# SolderDispenser_v1_3.net
KiCad netlist of a schematic drawn in EAGLE
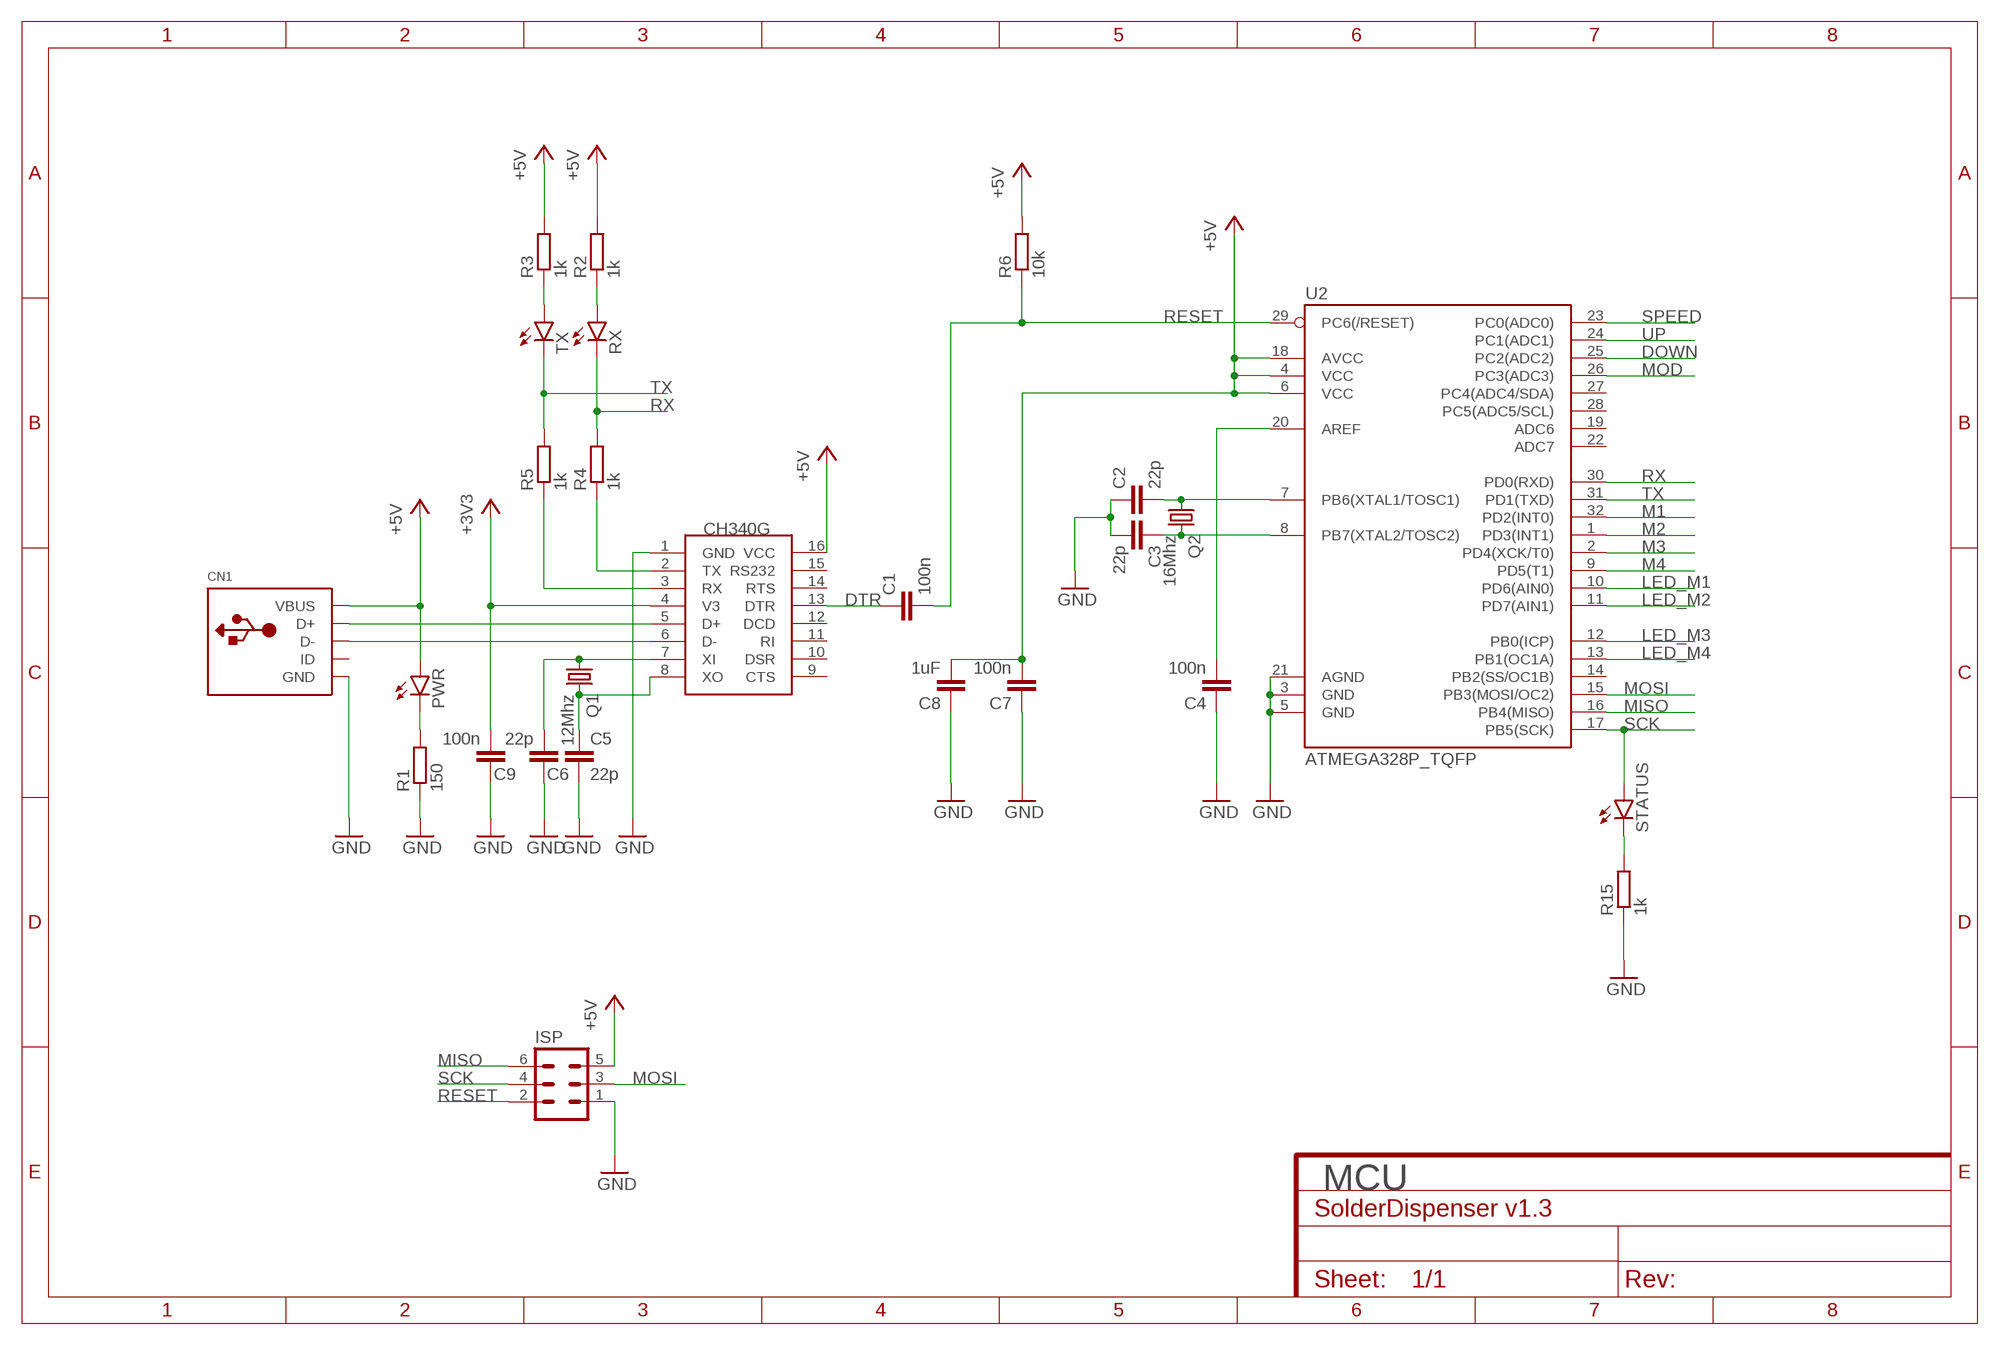
[diagram p0: schematic, sheet 1, part 1 of 2]
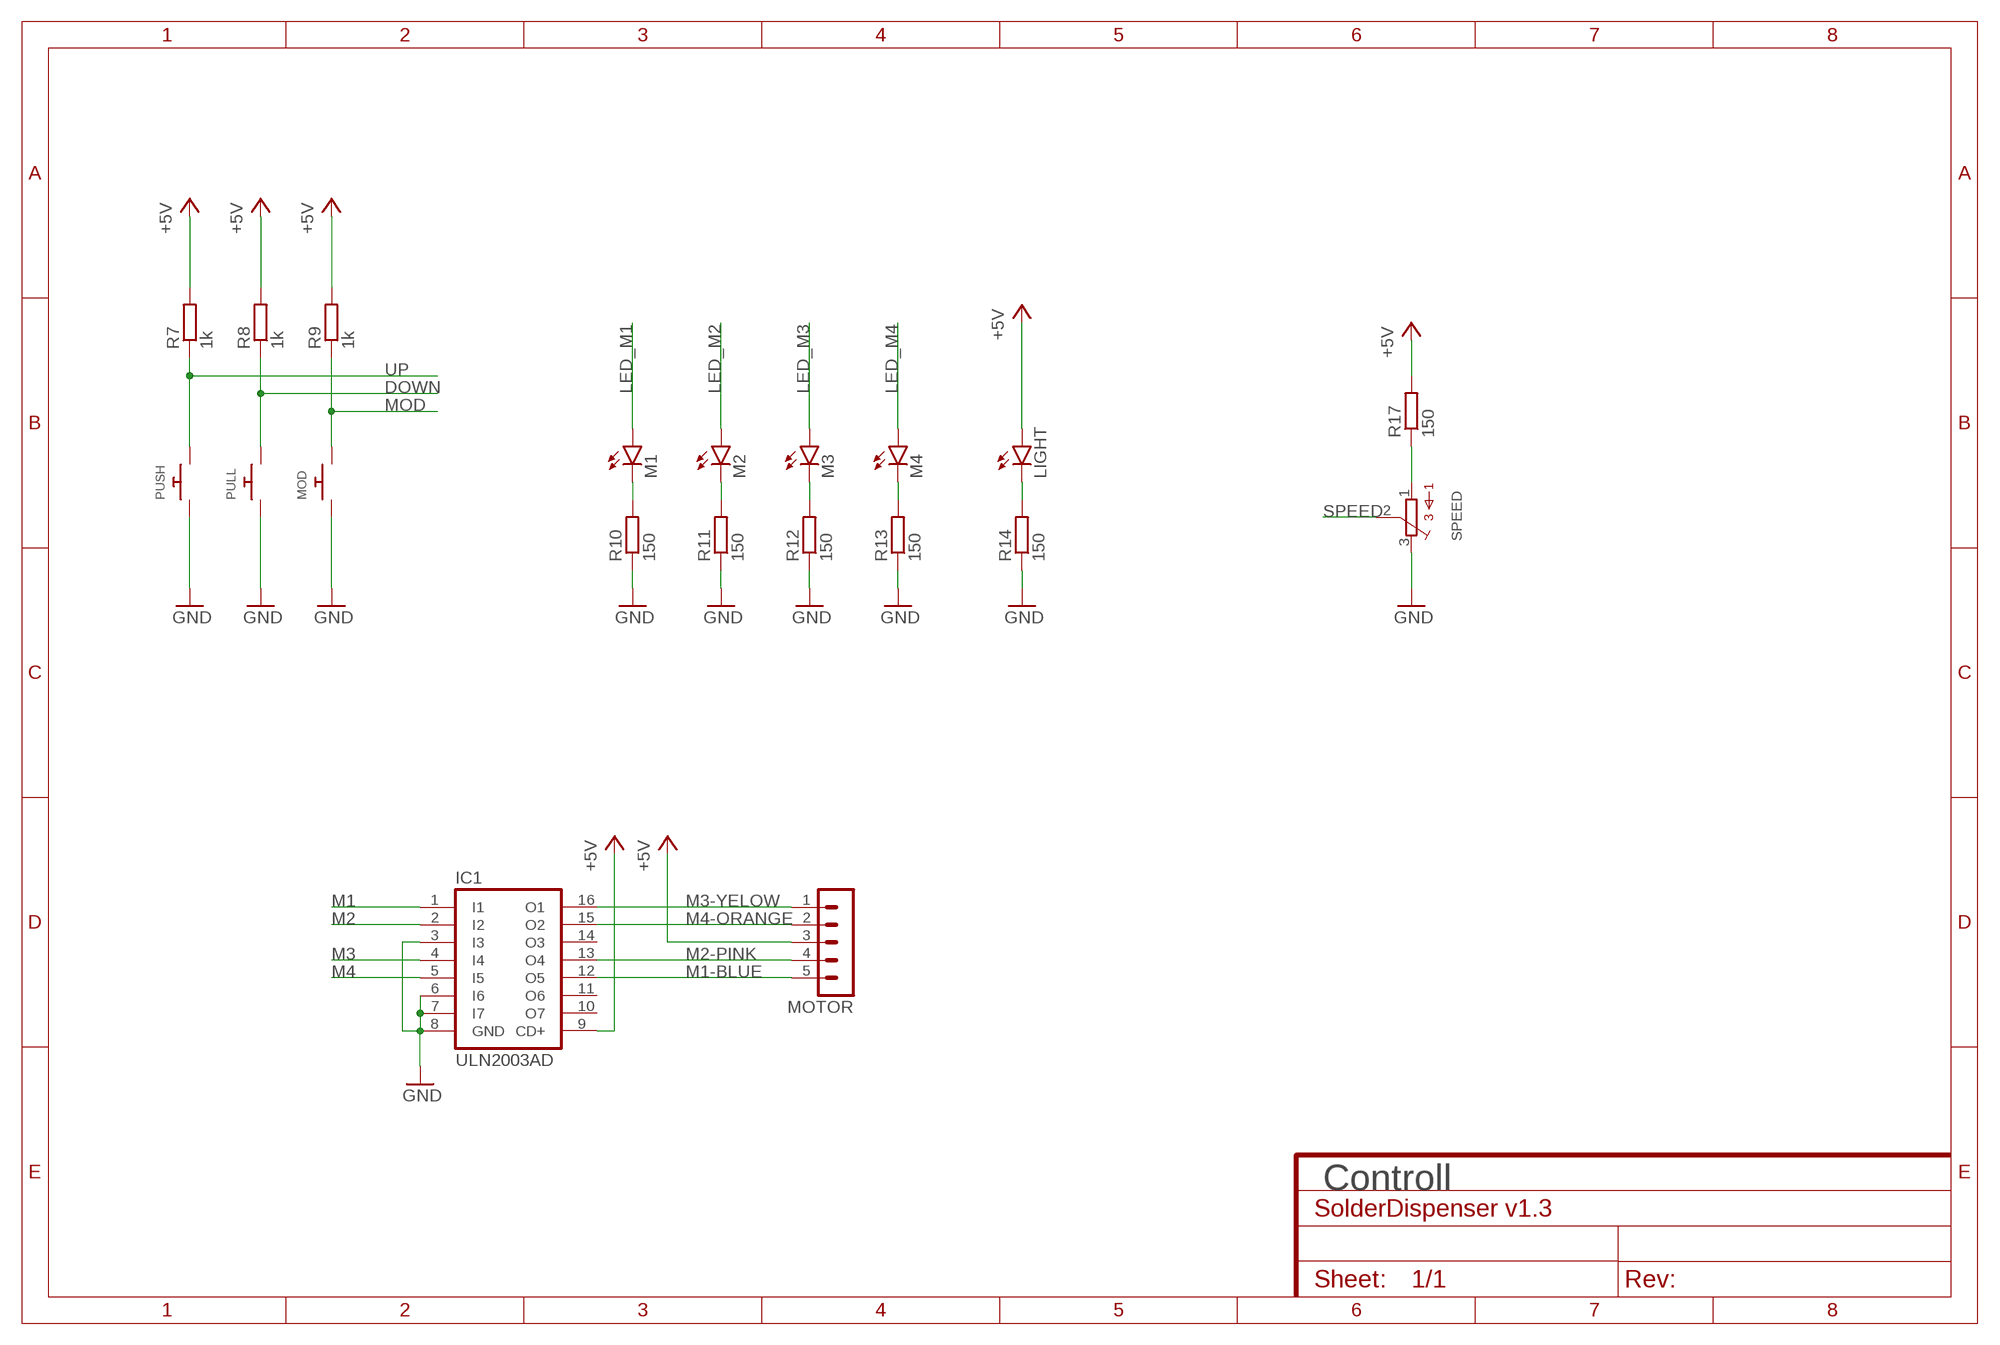
[diagram p1: schematic, sheet 1, part 2 of 2]

(export (version "E")
  (design (tool "Eeschema 10.0.6"))
  (components
    (comp (ref "C1")
      (value "100n")
      (footprint "eagle-import:C0805")
      (libsource (lib "eagle-import") (part "C-EUC0805"))
    )
    (comp (ref "C2")
      (value "22p")
      (footprint "eagle-import:C0805")
      (libsource (lib "eagle-import") (part "C-EUC0805"))
    )
    (comp (ref "C3")
      (value "22p")
      (footprint "eagle-import:C0805")
      (libsource (lib "eagle-import") (part "C-EUC0805"))
    )
    (comp (ref "C4")
      (value "100n")
      (footprint "eagle-import:C0805")
      (libsource (lib "eagle-import") (part "C-EUC0805"))
    )
    (comp (ref "C5")
      (value "22p")
      (footprint "eagle-import:C0805")
      (libsource (lib "eagle-import") (part "C-EUC0805"))
    )
    (comp (ref "C6")
      (value "22p")
      (footprint "eagle-import:C0805")
      (libsource (lib "eagle-import") (part "C-EUC0805"))
    )
    (comp (ref "C7")
      (value "100n")
      (footprint "eagle-import:C0805")
      (libsource (lib "eagle-import") (part "C-EUC0805"))
    )
    (comp (ref "C8")
      (value "1uF")
      (footprint "eagle-import:C0805")
      (libsource (lib "eagle-import") (part "C-EUC0805"))
    )
    (comp (ref "C9")
      (value "100n")
      (footprint "eagle-import:C0805")
      (libsource (lib "eagle-import") (part "C-EUC0805"))
    )
    (comp (ref "CN1")
      (value "USBMOLEX")
      (footprint "eagle-import:USB-MINIB-THM-MOLEX")
      (libsource (lib "eagle-import") (part "USBMOLEX"))
    )
    (comp (ref "IC1")
      (value "ULN2003AD")
      (footprint "eagle-import:SO16")
      (libsource (lib "eagle-import") (part "ULN2003AD"))
    )
    (comp (ref "ISP")
      (value "MA03-2")
      (footprint "eagle-import:MA03-2")
      (libsource (lib "eagle-import") (part "MA03-2"))
    )
    (comp (ref "LIGHT")
      (value "LED5MM")
      (footprint "eagle-import:LED5MM")
      (libsource (lib "eagle-import") (part "LED5MM"))
    )
    (comp (ref "M1")
      (value "LEDSML0805")
      (footprint "eagle-import:SML0805")
      (libsource (lib "eagle-import") (part "LEDSML0805"))
    )
    (comp (ref "M2")
      (value "LEDSML0805")
      (footprint "eagle-import:SML0805")
      (libsource (lib "eagle-import") (part "LEDSML0805"))
    )
    (comp (ref "M3")
      (value "LEDSML0805")
      (footprint "eagle-import:SML0805")
      (libsource (lib "eagle-import") (part "LEDSML0805"))
    )
    (comp (ref "M4")
      (value "LEDSML0805")
      (footprint "eagle-import:SML0805")
      (libsource (lib "eagle-import") (part "LEDSML0805"))
    )
    (comp (ref "MOD")
      (value "SWITCH_PUSHBUTTONEVQ-PE")
      (footprint "eagle-import:TACT_PANA-EVQ")
      (libsource (lib "eagle-import") (part "SWITCH_PUSHBUTTONEVQ-PE"))
    )
    (comp (ref "MOTOR")
      (value "MA05-1")
      (footprint "eagle-import:MA05-1")
      (libsource (lib "eagle-import") (part "MA05-1"))
    )
    (comp (ref "PULL")
      (value "SWITCH_PUSHBUTTONEVQ-PE")
      (footprint "eagle-import:TACT_PANA-EVQ")
      (libsource (lib "eagle-import") (part "SWITCH_PUSHBUTTONEVQ-PE"))
    )
    (comp (ref "PUSH")
      (value "SWITCH_PUSHBUTTONEVQ-PE")
      (footprint "eagle-import:TACT_PANA-EVQ")
      (libsource (lib "eagle-import") (part "SWITCH_PUSHBUTTONEVQ-PE"))
    )
    (comp (ref "PWR")
      (value "LEDSML0805")
      (footprint "eagle-import:SML0805")
      (libsource (lib "eagle-import") (part "LEDSML0805"))
    )
    (comp (ref "Q1")
      (value "12Mhz")
      (footprint "eagle-import:HC49UP")
      (libsource (lib "eagle-import") (part "CRYSTALHC49UP"))
    )
    (comp (ref "Q2")
      (value "16Mhz")
      (footprint "eagle-import:HC49UP")
      (libsource (lib "eagle-import") (part "CRYSTALHC49UP"))
    )
    (comp (ref "R1")
      (value "150")
      (footprint "eagle-import:R0805")
      (libsource (lib "eagle-import") (part "R-EU_R0805"))
    )
    (comp (ref "R2")
      (value "1k")
      (footprint "eagle-import:R0805")
      (libsource (lib "eagle-import") (part "R-EU_R0805"))
    )
    (comp (ref "R3")
      (value "1k")
      (footprint "eagle-import:R0805")
      (libsource (lib "eagle-import") (part "R-EU_R0805"))
    )
    (comp (ref "R4")
      (value "1k")
      (footprint "eagle-import:R0805")
      (libsource (lib "eagle-import") (part "R-EU_R0805"))
    )
    (comp (ref "R5")
      (value "1k")
      (footprint "eagle-import:R0805")
      (libsource (lib "eagle-import") (part "R-EU_R0805"))
    )
    (comp (ref "R6")
      (value "10k")
      (footprint "eagle-import:R0805")
      (libsource (lib "eagle-import") (part "R-EU_R0805"))
    )
    (comp (ref "R7")
      (value "1k")
      (footprint "eagle-import:R0805")
      (libsource (lib "eagle-import") (part "R-EU_R0805"))
    )
    (comp (ref "R8")
      (value "1k")
      (footprint "eagle-import:R0805")
      (libsource (lib "eagle-import") (part "R-EU_R0805"))
    )
    (comp (ref "R9")
      (value "1k")
      (footprint "eagle-import:R0805")
      (libsource (lib "eagle-import") (part "R-EU_R0805"))
    )
    (comp (ref "R10")
      (value "150")
      (footprint "eagle-import:R0805")
      (libsource (lib "eagle-import") (part "R-EU_R0805"))
    )
    (comp (ref "R11")
      (value "150")
      (footprint "eagle-import:R0805")
      (libsource (lib "eagle-import") (part "R-EU_R0805"))
    )
    (comp (ref "R12")
      (value "150")
      (footprint "eagle-import:R0805")
      (libsource (lib "eagle-import") (part "R-EU_R0805"))
    )
    (comp (ref "R13")
      (value "150")
      (footprint "eagle-import:R0805")
      (libsource (lib "eagle-import") (part "R-EU_R0805"))
    )
    (comp (ref "R14")
      (value "150")
      (footprint "eagle-import:R0805")
      (libsource (lib "eagle-import") (part "R-EU_R0805"))
    )
    (comp (ref "R15")
      (value "1k")
      (footprint "eagle-import:R0805")
      (libsource (lib "eagle-import") (part "R-EU_R0805"))
    )
    (comp (ref "R17")
      (value "150")
      (footprint "eagle-import:R0805")
      (libsource (lib "eagle-import") (part "R-EU_R0805"))
    )
    (comp (ref "RX")
      (value "LEDSML0805")
      (footprint "eagle-import:SML0805")
      (libsource (lib "eagle-import") (part "LEDSML0805"))
    )
    (comp (ref "SPEED")
      (value "3362P")
      (footprint "eagle-import:3362P")
      (libsource (lib "eagle-import") (part "3362P"))
    )
    (comp (ref "STATUS")
      (value "LEDSML0805")
      (footprint "eagle-import:SML0805")
      (libsource (lib "eagle-import") (part "LEDSML0805"))
    )
    (comp (ref "TX")
      (value "LEDSML0805")
      (footprint "eagle-import:SML0805")
      (libsource (lib "eagle-import") (part "LEDSML0805"))
    )
    (comp (ref "U$1")
      (value "CH340G")
      (footprint "eagle-import:SOIC16")
      (libsource (lib "eagle-import") (part "CH340G"))
    )
    (comp (ref "U2")
      (value "ATMEGA328P_TQFP")
      (footprint "eagle-import:TQFP32-08")
      (libsource (lib "eagle-import") (part "ATMEGA328P_TQFP"))
    )
  )
  (nets
    (net (code "1") (name "+3V3") (class "Default")
      (node (ref "C9") (pin "2") (pinfunction "2_2") (pintype "passive"))
      (node (ref "U$1") (pin "4") (pinfunction "V3_4") (pintype "bidirectional"))
    )
    (net (code "2") (name "+5V") (class "Default")
      (node (ref "C7") (pin "2") (pinfunction "2_2") (pintype "passive"))
      (node (ref "C8") (pin "2") (pinfunction "2_2") (pintype "passive"))
      (node (ref "CN1") (pin "VBUS") (pinfunction "VBUS_VBUS") (pintype "power_in"))
      (node (ref "IC1") (pin "9") (pinfunction "CD+_9") (pintype "passive"))
      (node (ref "ISP") (pin "5") (pinfunction "5_5") (pintype "passive"))
      (node (ref "LIGHT") (pin "A") (pinfunction "A_A") (pintype "passive"))
      (node (ref "MOTOR") (pin "3") (pinfunction "3_3") (pintype "passive"))
      (node (ref "PWR") (pin "A") (pinfunction "A_A") (pintype "passive"))
      (node (ref "R17") (pin "2") (pinfunction "2_2") (pintype "passive"))
      (node (ref "R2") (pin "2") (pinfunction "2_2") (pintype "passive"))
      (node (ref "R3") (pin "2") (pinfunction "2_2") (pintype "passive"))
      (node (ref "R6") (pin "2") (pinfunction "2_2") (pintype "passive"))
      (node (ref "R7") (pin "2") (pinfunction "2_2") (pintype "passive"))
      (node (ref "R8") (pin "2") (pinfunction "2_2") (pintype "passive"))
      (node (ref "R9") (pin "2") (pinfunction "2_2") (pintype "passive"))
      (node (ref "U$1") (pin "16") (pinfunction "VCC_16") (pintype "bidirectional"))
      (node (ref "U2") (pin "18") (pinfunction "AVCC_18") (pintype "bidirectional"))
      (node (ref "U2") (pin "4") (pinfunction "VCC_4") (pintype "bidirectional"))
      (node (ref "U2") (pin "6") (pinfunction "VCC_6") (pintype "bidirectional"))
    )
    (net (code "3") (name "/DOWN") (class "Default")
      (node (ref "PULL") (pin "P$2") (pinfunction "P$2_P$2") (pintype "passive"))
      (node (ref "R8") (pin "1") (pinfunction "1_1") (pintype "passive"))
      (node (ref "U2") (pin "25") (pinfunction "PC2(ADC2)_25") (pintype "bidirectional"))
    )
    (net (code "4") (name "/DTR") (class "Default")
      (node (ref "C1") (pin "1") (pinfunction "1_1") (pintype "passive"))
      (node (ref "U$1") (pin "13") (pinfunction "DTR_13") (pintype "bidirectional"))
    )
    (net (code "5") (name "/LED_M1") (class "Default")
      (node (ref "M1") (pin "A") (pinfunction "A_A") (pintype "passive"))
      (node (ref "U2") (pin "10") (pinfunction "PD6(AIN0)_10") (pintype "bidirectional"))
    )
    (net (code "6") (name "/LED_M2") (class "Default")
      (node (ref "M2") (pin "A") (pinfunction "A_A") (pintype "passive"))
      (node (ref "U2") (pin "11") (pinfunction "PD7(AIN1)_11") (pintype "bidirectional"))
    )
    (net (code "7") (name "/LED_M3") (class "Default")
      (node (ref "M3") (pin "A") (pinfunction "A_A") (pintype "passive"))
      (node (ref "U2") (pin "12") (pinfunction "PB0(ICP)_12") (pintype "bidirectional"))
    )
    (net (code "8") (name "/LED_M4") (class "Default")
      (node (ref "M4") (pin "A") (pinfunction "A_A") (pintype "passive"))
      (node (ref "U2") (pin "13") (pinfunction "PB1(OC1A)_13") (pintype "bidirectional"))
    )
    (net (code "9") (name "/M1") (class "Default")
      (node (ref "IC1") (pin "1") (pinfunction "I1_1") (pintype "input"))
      (node (ref "U2") (pin "32") (pinfunction "PD2(INT0)_32") (pintype "bidirectional"))
    )
    (net (code "10") (name "/M1-BLUE") (class "Default")
      (node (ref "IC1") (pin "12") (pinfunction "O5_12") (pintype "open_collector"))
      (node (ref "MOTOR") (pin "5") (pinfunction "5_5") (pintype "passive"))
    )
    (net (code "11") (name "/M2") (class "Default")
      (node (ref "IC1") (pin "2") (pinfunction "I2_2") (pintype "input"))
      (node (ref "U2") (pin "1") (pinfunction "PD3(INT1)_1") (pintype "bidirectional"))
    )
    (net (code "12") (name "/M2-PINK") (class "Default")
      (node (ref "IC1") (pin "13") (pinfunction "O4_13") (pintype "open_collector"))
      (node (ref "MOTOR") (pin "4") (pinfunction "4_4") (pintype "passive"))
    )
    (net (code "13") (name "/M3") (class "Default")
      (node (ref "IC1") (pin "4") (pinfunction "I4_4") (pintype "input"))
      (node (ref "U2") (pin "2") (pinfunction "PD4(XCK/T0)_2") (pintype "bidirectional"))
    )
    (net (code "14") (name "/M3-YELOW") (class "Default")
      (node (ref "IC1") (pin "16") (pinfunction "O1_16") (pintype "open_collector"))
      (node (ref "MOTOR") (pin "1") (pinfunction "1_1") (pintype "passive"))
    )
    (net (code "15") (name "/M4") (class "Default")
      (node (ref "IC1") (pin "5") (pinfunction "I5_5") (pintype "input"))
      (node (ref "U2") (pin "9") (pinfunction "PD5(T1)_9") (pintype "bidirectional"))
    )
    (net (code "16") (name "/M4-ORANGE") (class "Default")
      (node (ref "IC1") (pin "15") (pinfunction "O2_15") (pintype "open_collector"))
      (node (ref "MOTOR") (pin "2") (pinfunction "2_2") (pintype "passive"))
    )
    (net (code "17") (name "/MISO") (class "Default")
      (node (ref "ISP") (pin "6") (pinfunction "6_6") (pintype "passive"))
      (node (ref "U2") (pin "16") (pinfunction "PB4(MISO)_16") (pintype "bidirectional"))
    )
    (net (code "18") (name "/MOD") (class "Default")
      (node (ref "MOD") (pin "P$2") (pinfunction "P$2_P$2") (pintype "passive"))
      (node (ref "R9") (pin "1") (pinfunction "1_1") (pintype "passive"))
      (node (ref "U2") (pin "26") (pinfunction "PC3(ADC3)_26") (pintype "bidirectional"))
    )
    (net (code "19") (name "/MOSI") (class "Default")
      (node (ref "ISP") (pin "3") (pinfunction "3_3") (pintype "passive"))
      (node (ref "U2") (pin "15") (pinfunction "PB3(MOSI/OC2)_15") (pintype "bidirectional"))
    )
    (net (code "20") (name "/RESET") (class "Default")
      (node (ref "C1") (pin "2") (pinfunction "2_2") (pintype "passive"))
      (node (ref "ISP") (pin "2") (pinfunction "2_2") (pintype "passive"))
      (node (ref "R6") (pin "1") (pinfunction "1_1") (pintype "passive"))
      (node (ref "U2") (pin "29") (pinfunction "PC6(/RESET)_29") (pintype "bidirectional"))
    )
    (net (code "21") (name "/RX") (class "Default")
      (node (ref "R4") (pin "2") (pinfunction "2_2") (pintype "passive"))
      (node (ref "RX") (pin "C") (pinfunction "C_C") (pintype "passive"))
      (node (ref "U2") (pin "30") (pinfunction "PD0(RXD)_30") (pintype "bidirectional"))
    )
    (net (code "22") (name "/SCK") (class "Default")
      (node (ref "ISP") (pin "4") (pinfunction "4_4") (pintype "passive"))
      (node (ref "STATUS") (pin "A") (pinfunction "A_A") (pintype "passive"))
      (node (ref "U2") (pin "17") (pinfunction "PB5(SCK)_17") (pintype "bidirectional"))
    )
    (net (code "23") (name "/SPEED") (class "Default")
      (node (ref "SPEED") (pin "2") (pinfunction "2_2") (pintype "passive"))
      (node (ref "U2") (pin "23") (pinfunction "PC0(ADC0)_23") (pintype "bidirectional"))
    )
    (net (code "24") (name "/TX") (class "Default")
      (node (ref "R5") (pin "2") (pinfunction "2_2") (pintype "passive"))
      (node (ref "TX") (pin "C") (pinfunction "C_C") (pintype "passive"))
      (node (ref "U2") (pin "31") (pinfunction "PD1(TXD)_31") (pintype "bidirectional"))
    )
    (net (code "25") (name "/UP") (class "Default")
      (node (ref "PUSH") (pin "P$2") (pinfunction "P$2_P$2") (pintype "passive"))
      (node (ref "R7") (pin "1") (pinfunction "1_1") (pintype "passive"))
      (node (ref "U2") (pin "24") (pinfunction "PC1(ADC1)_24") (pintype "bidirectional"))
    )
    (net (code "26") (name "GND") (class "Default")
      (node (ref "C2") (pin "1") (pinfunction "1_1") (pintype "passive"))
      (node (ref "C3") (pin "2") (pinfunction "2_2") (pintype "passive"))
      (node (ref "C4") (pin "1") (pinfunction "1_1") (pintype "passive"))
      (node (ref "C5") (pin "2") (pinfunction "2_2") (pintype "passive"))
      (node (ref "C6") (pin "1") (pinfunction "1_1") (pintype "passive"))
      (node (ref "C7") (pin "1") (pinfunction "1_1") (pintype "passive"))
      (node (ref "C8") (pin "1") (pinfunction "1_1") (pintype "passive"))
      (node (ref "C9") (pin "1") (pinfunction "1_1") (pintype "passive"))
      (node (ref "CN1") (pin "GND") (pinfunction "GND_GND") (pintype "power_in"))
      (node (ref "IC1") (pin "3") (pinfunction "I3_3") (pintype "input"))
      (node (ref "IC1") (pin "6") (pinfunction "I6_6") (pintype "input"))
      (node (ref "IC1") (pin "7") (pinfunction "I7_7") (pintype "input"))
      (node (ref "IC1") (pin "8") (pinfunction "GND_8") (pintype "power_in"))
      (node (ref "ISP") (pin "1") (pinfunction "1_1") (pintype "passive"))
      (node (ref "MOD") (pin "P$1") (pinfunction "P$1_P$1") (pintype "passive"))
      (node (ref "PULL") (pin "P$1") (pinfunction "P$1_P$1") (pintype "passive"))
      (node (ref "PUSH") (pin "P$1") (pinfunction "P$1_P$1") (pintype "passive"))
      (node (ref "R1") (pin "1") (pinfunction "1_1") (pintype "passive"))
      (node (ref "R10") (pin "1") (pinfunction "1_1") (pintype "passive"))
      (node (ref "R11") (pin "1") (pinfunction "1_1") (pintype "passive"))
      (node (ref "R12") (pin "1") (pinfunction "1_1") (pintype "passive"))
      (node (ref "R13") (pin "1") (pinfunction "1_1") (pintype "passive"))
      (node (ref "R14") (pin "1") (pinfunction "1_1") (pintype "passive"))
      (node (ref "R15") (pin "1") (pinfunction "1_1") (pintype "passive"))
      (node (ref "SPEED") (pin "3") (pinfunction "3_3") (pintype "passive"))
      (node (ref "U$1") (pin "1") (pinfunction "GND_1") (pintype "bidirectional"))
      (node (ref "U2") (pin "21") (pinfunction "AGND_21") (pintype "bidirectional"))
      (node (ref "U2") (pin "3") (pinfunction "GND_3") (pintype "bidirectional"))
      (node (ref "U2") (pin "5") (pinfunction "GND_5") (pintype "bidirectional"))
    )
    (net (code "27") (name "Net-(LIGHT-C)") (class "Default")
      (node (ref "LIGHT") (pin "K") (pinfunction "C_K") (pintype "passive"))
      (node (ref "R14") (pin "2") (pinfunction "2_2") (pintype "passive"))
    )
    (net (code "28") (name "Net-(M1-PadC)") (class "Default")
      (node (ref "M1") (pin "C") (pinfunction "C_C") (pintype "passive"))
      (node (ref "R10") (pin "2") (pinfunction "2_2") (pintype "passive"))
    )
    (net (code "29") (name "Net-(M2-PadC)") (class "Default")
      (node (ref "M2") (pin "C") (pinfunction "C_C") (pintype "passive"))
      (node (ref "R11") (pin "2") (pinfunction "2_2") (pintype "passive"))
    )
    (net (code "30") (name "Net-(M3-PadC)") (class "Default")
      (node (ref "M3") (pin "C") (pinfunction "C_C") (pintype "passive"))
      (node (ref "R12") (pin "2") (pinfunction "2_2") (pintype "passive"))
    )
    (net (code "31") (name "Net-(M4-PadC)") (class "Default")
      (node (ref "M4") (pin "C") (pinfunction "C_C") (pintype "passive"))
      (node (ref "R13") (pin "2") (pinfunction "2_2") (pintype "passive"))
    )
    (net (code "32") (name "Net-(PWR-PadC)") (class "Default")
      (node (ref "PWR") (pin "C") (pinfunction "C_C") (pintype "passive"))
      (node (ref "R1") (pin "2") (pinfunction "2_2") (pintype "passive"))
    )
    (net (code "33") (name "Net-(R2-Pad1)") (class "Default")
      (node (ref "R2") (pin "1") (pinfunction "1_1") (pintype "passive"))
      (node (ref "RX") (pin "A") (pinfunction "A_A") (pintype "passive"))
    )
    (net (code "34") (name "Net-(R3-Pad1)") (class "Default")
      (node (ref "R3") (pin "1") (pinfunction "1_1") (pintype "passive"))
      (node (ref "TX") (pin "A") (pinfunction "A_A") (pintype "passive"))
    )
    (net (code "35") (name "Net-(R15-Pad2)") (class "Default")
      (node (ref "R15") (pin "2") (pinfunction "2_2") (pintype "passive"))
      (node (ref "STATUS") (pin "C") (pinfunction "C_C") (pintype "passive"))
    )
    (net (code "36") (name "Net-(R17-Pad1)") (class "Default")
      (node (ref "R17") (pin "1") (pinfunction "1_1") (pintype "passive"))
      (node (ref "SPEED") (pin "1") (pinfunction "1_1") (pintype "passive"))
    )
    (net (code "37") (name "Net-(U$1-D+)") (class "Default")
      (node (ref "CN1") (pin "D+") (pinfunction "D+_D+") (pintype "bidirectional"))
      (node (ref "U$1") (pin "5") (pinfunction "D+_5") (pintype "bidirectional"))
    )
    (net (code "38") (name "Net-(U$1-D-)") (class "Default")
      (node (ref "CN1") (pin "D-") (pinfunction "D-_D-") (pintype "bidirectional"))
      (node (ref "U$1") (pin "6") (pinfunction "D-_6") (pintype "bidirectional"))
    )
    (net (code "39") (name "Net-(U$1-RX)") (class "Default")
      (node (ref "R5") (pin "1") (pinfunction "1_1") (pintype "passive"))
      (node (ref "U$1") (pin "3") (pinfunction "RX_3") (pintype "bidirectional"))
    )
    (net (code "40") (name "Net-(U$1-TX)") (class "Default")
      (node (ref "R4") (pin "1") (pinfunction "1_1") (pintype "passive"))
      (node (ref "U$1") (pin "2") (pinfunction "TX_2") (pintype "bidirectional"))
    )
    (net (code "41") (name "Net-(U$1-XI)") (class "Default")
      (node (ref "C6") (pin "2") (pinfunction "2_2") (pintype "passive"))
      (node (ref "Q1") (pin "1") (pinfunction "1_1") (pintype "passive"))
      (node (ref "U$1") (pin "7") (pinfunction "XI_7") (pintype "bidirectional"))
    )
    (net (code "42") (name "Net-(U$1-XO)") (class "Default")
      (node (ref "C5") (pin "1") (pinfunction "1_1") (pintype "passive"))
      (node (ref "Q1") (pin "2") (pinfunction "2_2") (pintype "passive"))
      (node (ref "U$1") (pin "8") (pinfunction "XO_8") (pintype "bidirectional"))
    )
    (net (code "43") (name "Net-(U2-AREF)") (class "Default")
      (node (ref "C4") (pin "2") (pinfunction "2_2") (pintype "passive"))
      (node (ref "U2") (pin "20") (pinfunction "AREF_20") (pintype "bidirectional"))
    )
    (net (code "44") (name "Net-(U2-PB6(XTAL1{slash}TOSC1))") (class "Default")
      (node (ref "C2") (pin "2") (pinfunction "2_2") (pintype "passive"))
      (node (ref "Q2") (pin "1") (pinfunction "1_1") (pintype "passive"))
      (node (ref "U2") (pin "7") (pinfunction "PB6(XTAL1/TOSC1)_7") (pintype "bidirectional"))
    )
    (net (code "45") (name "Net-(U2-PB7(XTAL2{slash}TOSC2))") (class "Default")
      (node (ref "C3") (pin "1") (pinfunction "1_1") (pintype "passive"))
      (node (ref "Q2") (pin "2") (pinfunction "2_2") (pintype "passive"))
      (node (ref "U2") (pin "8") (pinfunction "PB7(XTAL2/TOSC2)_8") (pintype "bidirectional"))
    )
    (net (code "46") (name "unconnected-(CN1-PadID)") (class "Default")
      (node (ref "CN1") (pin "ID") (pinfunction "ID_ID") (pintype "bidirectional"))
    )
    (net (code "47") (name "unconnected-(IC1-O3-Pad14)") (class "Default")
      (node (ref "IC1") (pin "14") (pinfunction "O3_14") (pintype "open_collector"))
    )
    (net (code "48") (name "unconnected-(IC1-O6-Pad11)") (class "Default")
      (node (ref "IC1") (pin "11") (pinfunction "O6_11") (pintype "open_collector"))
    )
    (net (code "49") (name "unconnected-(IC1-O7-Pad10)") (class "Default")
      (node (ref "IC1") (pin "10") (pinfunction "O7_10") (pintype "open_collector"))
    )
    (net (code "50") (name "unconnected-(U$1-CTS-Pad9)") (class "Default")
      (node (ref "U$1") (pin "9") (pinfunction "CTS_9") (pintype "bidirectional"))
    )
    (net (code "51") (name "unconnected-(U$1-DCD-Pad12)") (class "Default")
      (node (ref "U$1") (pin "12") (pinfunction "DCD_12") (pintype "bidirectional"))
    )
    (net (code "52") (name "unconnected-(U$1-DSR-Pad10)") (class "Default")
      (node (ref "U$1") (pin "10") (pinfunction "DSR_10") (pintype "bidirectional"))
    )
    (net (code "53") (name "unconnected-(U$1-RI-Pad11)") (class "Default")
      (node (ref "U$1") (pin "11") (pinfunction "RI_11") (pintype "bidirectional"))
    )
    (net (code "54") (name "unconnected-(U$1-RS232-Pad15)") (class "Default")
      (node (ref "U$1") (pin "15") (pinfunction "RS232_15") (pintype "bidirectional"))
    )
    (net (code "55") (name "unconnected-(U$1-RTS-Pad14)") (class "Default")
      (node (ref "U$1") (pin "14") (pinfunction "RTS_14") (pintype "bidirectional"))
    )
    (net (code "56") (name "unconnected-(U2-ADC6-Pad19)") (class "Default")
      (node (ref "U2") (pin "19") (pinfunction "ADC6_19") (pintype "bidirectional"))
    )
    (net (code "57") (name "unconnected-(U2-ADC7-Pad22)") (class "Default")
      (node (ref "U2") (pin "22") (pinfunction "ADC7_22") (pintype "bidirectional"))
    )
    (net (code "58") (name "unconnected-(U2-PB2(SS{slash}OC1B)-Pad14)") (class "Default")
      (node (ref "U2") (pin "14") (pinfunction "PB2(SS/OC1B)_14") (pintype "bidirectional"))
    )
    (net (code "59") (name "unconnected-(U2-PC4(ADC4{slash}SDA)-Pad27)") (class "Default")
      (node (ref "U2") (pin "27") (pinfunction "PC4(ADC4/SDA)_27") (pintype "bidirectional"))
    )
    (net (code "60") (name "unconnected-(U2-PC5(ADC5{slash}SCL)-Pad28)") (class "Default")
      (node (ref "U2") (pin "28") (pinfunction "PC5(ADC5/SCL)_28") (pintype "bidirectional"))
    )
  )
)
